# buttonModule.net
KiCad netlist of a schematic drawn in EAGLE
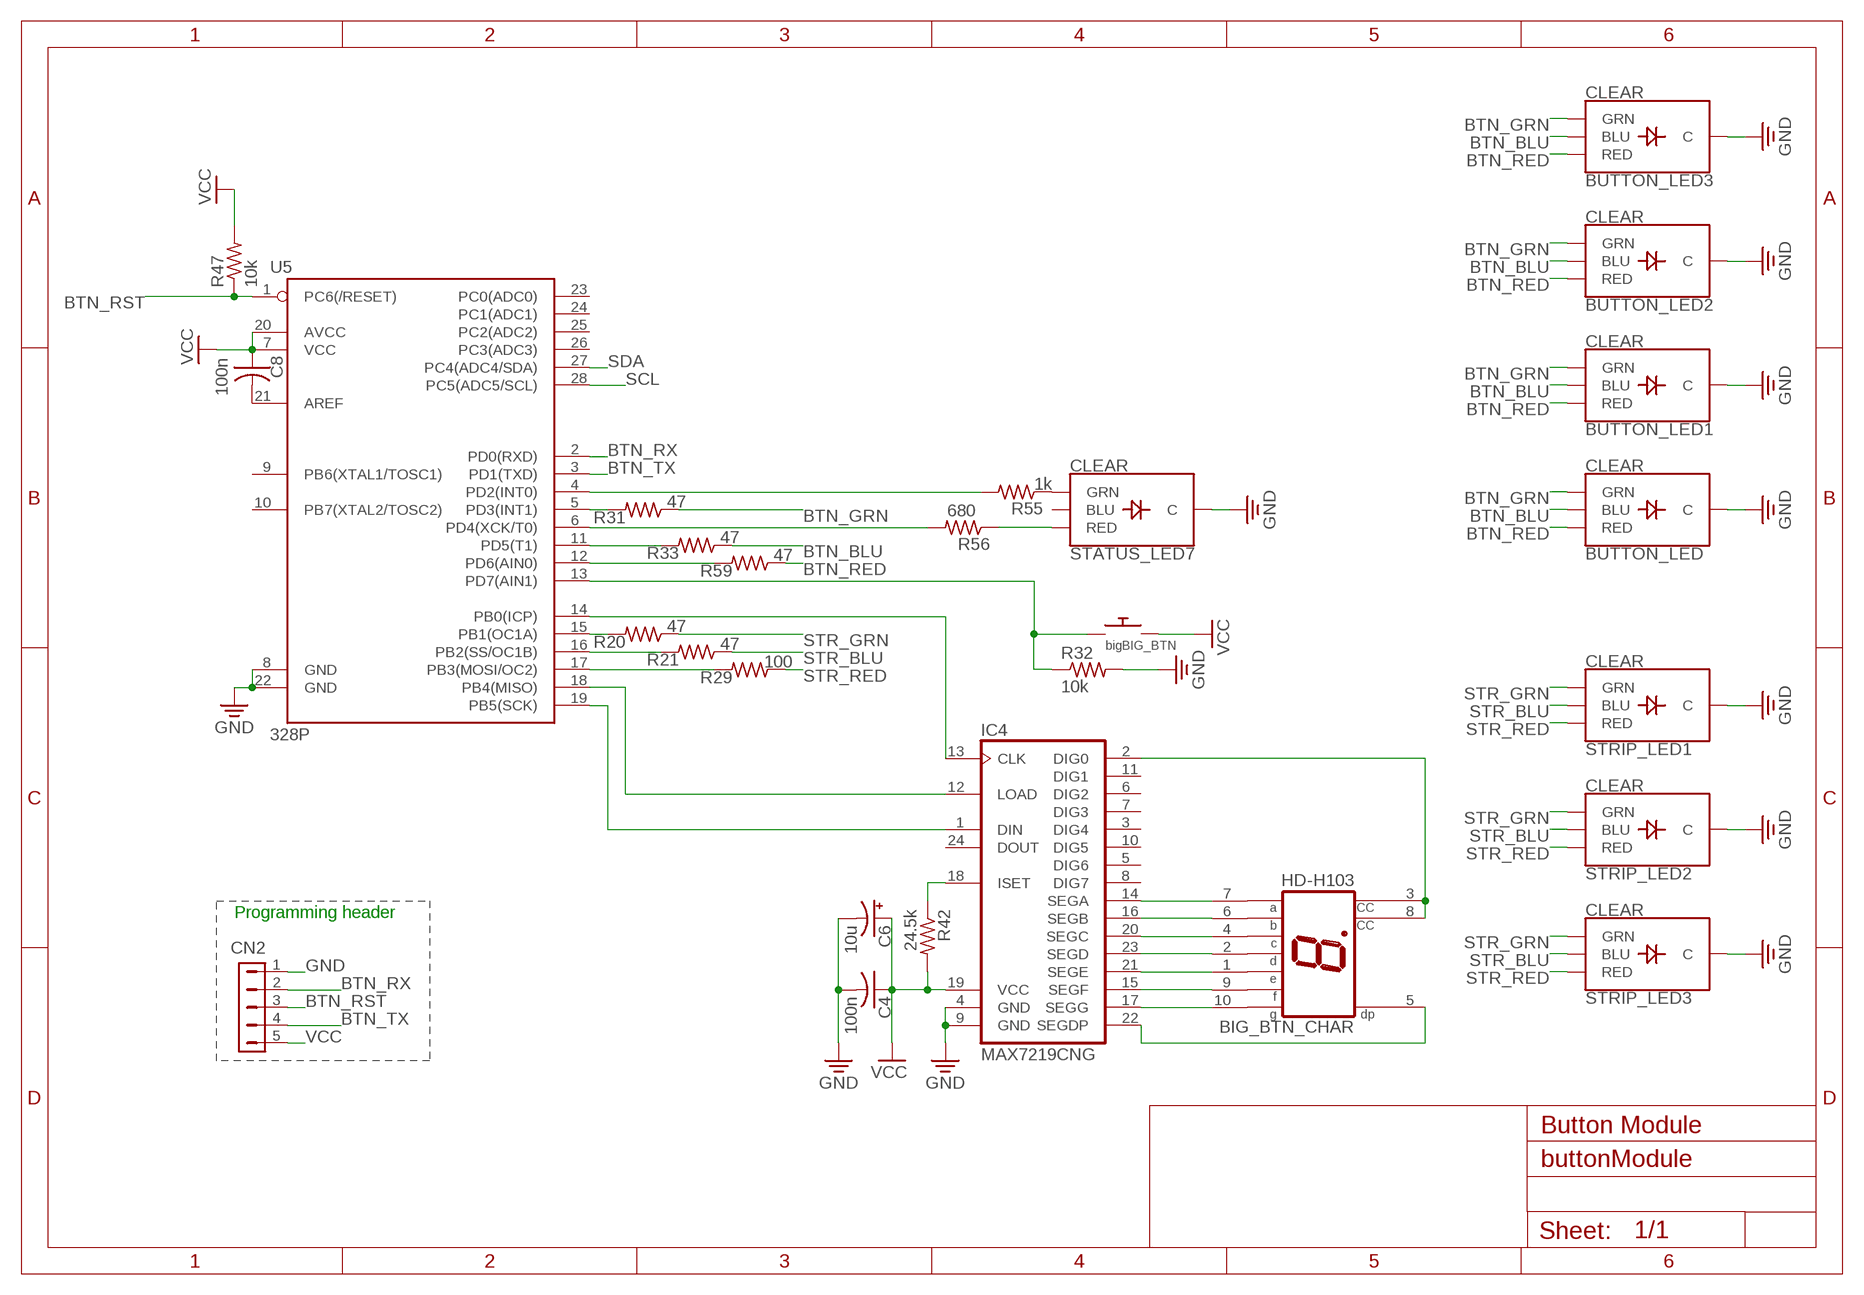
[diagram p0: schematic, sheet 1]

(export (version "E")
  (design (tool "Eeschema 10.0.6"))
  (components
    (comp (ref "BIG_BTN")
      (value "big")
      (footprint "eagle-import:TACT_PANA-EVQ")
      (libsource (lib "eagle-import") (part "SWITCH_PUSHBUTTONEVQ-PE"))
    )
    (comp (ref "BIG_BTN_CHAR")
      (value "HD-H103")
      (footprint "eagle-import:HDSP-M")
      (libsource (lib "eagle-import") (part "HD-H103"))
    )
    (comp (ref "BUTTON_LED")
      (value "CLEAR")
      (footprint "eagle-import:LED-RGB-THRU")
      (libsource (lib "eagle-import") (part "LED-RGB-CCCLEAR"))
    )
    (comp (ref "BUTTON_LED1")
      (value "CLEAR")
      (footprint "eagle-import:LED-RGB-THRU")
      (libsource (lib "eagle-import") (part "LED-RGB-CCCLEAR"))
    )
    (comp (ref "BUTTON_LED2")
      (value "CLEAR")
      (footprint "eagle-import:LED-RGB-THRU")
      (libsource (lib "eagle-import") (part "LED-RGB-CCCLEAR"))
    )
    (comp (ref "BUTTON_LED3")
      (value "CLEAR")
      (footprint "eagle-import:LED-RGB-THRU")
      (libsource (lib "eagle-import") (part "LED-RGB-CCCLEAR"))
    )
    (comp (ref "C4")
      (value "100n")
      (footprint "eagle-import:C025-024X044")
      (libsource (lib "eagle-import") (part "C-US025-024X044"))
    )
    (comp (ref "C6")
      (value "10u")
      (footprint "eagle-import:085CS_1AR")
      (libsource (lib "eagle-import") (part "CPOL-US085CS-1AR"))
    )
    (comp (ref "C8")
      (value "100n")
      (footprint "eagle-import:C025-024X044")
      (libsource (lib "eagle-import") (part "C-US025-024X044"))
    )
    (comp (ref "CN2")
      (value "HDR-1X5-SIP-100")
      (footprint "eagle-import:SIP-100-5V")
      (libsource (lib "eagle-import") (part "HDR-1X5-SIP-100"))
    )
    (comp (ref "IC4")
      (value "MAX7219CNG")
      (footprint "eagle-import:DIL24-3")
      (fields (field (name "MF") "MAXIM"))
      (libsource (lib "eagle-import") (part "MAX7219CNG"))
    )
    (comp (ref "R20")
      (value "47")
      (footprint "eagle-import:0805-THM")
      (libsource (lib "eagle-import") (part "FLIPFLOP-RES"))
    )
    (comp (ref "R21")
      (value "47")
      (footprint "eagle-import:0805-THM")
      (libsource (lib "eagle-import") (part "FLIPFLOP-RES"))
    )
    (comp (ref "R29")
      (value "100")
      (footprint "eagle-import:0805-THM")
      (libsource (lib "eagle-import") (part "FLIPFLOP-RES"))
    )
    (comp (ref "R31")
      (value "47")
      (footprint "eagle-import:0805-THM")
      (libsource (lib "eagle-import") (part "FLIPFLOP-RES"))
    )
    (comp (ref "R32")
      (value "10k")
      (footprint "eagle-import:0309_12")
      (libsource (lib "eagle-import") (part "R-US_0309/12"))
    )
    (comp (ref "R33")
      (value "47")
      (footprint "eagle-import:0805-THM")
      (libsource (lib "eagle-import") (part "FLIPFLOP-RES"))
    )
    (comp (ref "R42")
      (value "24.5k")
      (footprint "eagle-import:0309_12")
      (libsource (lib "eagle-import") (part "R-US_0309/12"))
    )
    (comp (ref "R47")
      (value "10k")
      (footprint "eagle-import:0309_12")
      (libsource (lib "eagle-import") (part "R-US_0309/12"))
    )
    (comp (ref "R55")
      (value "1k")
      (footprint "eagle-import:0805-THM")
      (libsource (lib "eagle-import") (part "FLIPFLOP-RES"))
    )
    (comp (ref "R56")
      (value "680")
      (footprint "eagle-import:0805-THM")
      (libsource (lib "eagle-import") (part "FLIPFLOP-RES"))
    )
    (comp (ref "R59")
      (value "47")
      (footprint "eagle-import:0805-THM")
      (libsource (lib "eagle-import") (part "FLIPFLOP-RES"))
    )
    (comp (ref "STATUS_LED7")
      (value "CLEAR")
      (footprint "eagle-import:LED-RGB-THRU")
      (libsource (lib "eagle-import") (part "LED-RGB-CCCLEAR"))
    )
    (comp (ref "STRIP_LED1")
      (value "CLEAR")
      (footprint "eagle-import:LED-RGB-THRU")
      (libsource (lib "eagle-import") (part "LED-RGB-CCCLEAR"))
    )
    (comp (ref "STRIP_LED2")
      (value "CLEAR")
      (footprint "eagle-import:LED-RGB-THRU")
      (libsource (lib "eagle-import") (part "LED-RGB-CCCLEAR"))
    )
    (comp (ref "STRIP_LED3")
      (value "CLEAR")
      (footprint "eagle-import:LED-RGB-THRU")
      (libsource (lib "eagle-import") (part "LED-RGB-CCCLEAR"))
    )
    (comp (ref "U5")
      (value "328P")
      (footprint "eagle-import:DIP28")
      (libsource (lib "eagle-import") (part "ATMEGA328P_PDIP"))
    )
  )
  (nets
    (net (code "1") (name "/BTN_BLU") (class "Default")
      (node (ref "BUTTON_LED") (pin "4") (pinfunction "BLU_4") (pintype "bidirectional"))
      (node (ref "BUTTON_LED1") (pin "4") (pinfunction "BLU_4") (pintype "bidirectional"))
      (node (ref "BUTTON_LED2") (pin "4") (pinfunction "BLU_4") (pintype "bidirectional"))
      (node (ref "BUTTON_LED3") (pin "4") (pinfunction "BLU_4") (pintype "bidirectional"))
      (node (ref "R33") (pin "1") (pinfunction "1_1") (pintype "passive"))
    )
    (net (code "2") (name "/BTN_GRN") (class "Default")
      (node (ref "BUTTON_LED") (pin "3") (pinfunction "GRN_3") (pintype "bidirectional"))
      (node (ref "BUTTON_LED1") (pin "3") (pinfunction "GRN_3") (pintype "bidirectional"))
      (node (ref "BUTTON_LED2") (pin "3") (pinfunction "GRN_3") (pintype "bidirectional"))
      (node (ref "BUTTON_LED3") (pin "3") (pinfunction "GRN_3") (pintype "bidirectional"))
      (node (ref "R31") (pin "1") (pinfunction "1_1") (pintype "passive"))
    )
    (net (code "3") (name "/BTN_RED") (class "Default")
      (node (ref "BUTTON_LED") (pin "1") (pinfunction "RED_1") (pintype "bidirectional"))
      (node (ref "BUTTON_LED1") (pin "1") (pinfunction "RED_1") (pintype "bidirectional"))
      (node (ref "BUTTON_LED2") (pin "1") (pinfunction "RED_1") (pintype "bidirectional"))
      (node (ref "BUTTON_LED3") (pin "1") (pinfunction "RED_1") (pintype "bidirectional"))
      (node (ref "R59") (pin "1") (pinfunction "1_1") (pintype "passive"))
    )
    (net (code "4") (name "/BTN_RST") (class "Default")
      (node (ref "CN2") (pin "3") (pinfunction "3_3") (pintype "passive"))
      (node (ref "R47") (pin "1") (pinfunction "1_1") (pintype "passive"))
      (node (ref "U5") (pin "1") (pinfunction "PC6(/RESET)_1") (pintype "bidirectional"))
    )
    (net (code "5") (name "/BTN_RX") (class "Default")
      (node (ref "CN2") (pin "2") (pinfunction "2_2") (pintype "passive"))
      (node (ref "U5") (pin "2") (pinfunction "PD0(RXD)_2") (pintype "bidirectional"))
    )
    (net (code "6") (name "/BTN_TX") (class "Default")
      (node (ref "CN2") (pin "4") (pinfunction "4_4") (pintype "passive"))
      (node (ref "U5") (pin "3") (pinfunction "PD1(TXD)_3") (pintype "bidirectional"))
    )
    (net (code "7") (name "/SCL") (class "Default")
      (node (ref "U5") (pin "28") (pinfunction "PC5(ADC5/SCL)_28") (pintype "bidirectional"))
    )
    (net (code "8") (name "/SDA") (class "Default")
      (node (ref "U5") (pin "27") (pinfunction "PC4(ADC4/SDA)_27") (pintype "bidirectional"))
    )
    (net (code "9") (name "/STR_BLU") (class "Default")
      (node (ref "R21") (pin "1") (pinfunction "1_1") (pintype "passive"))
      (node (ref "STRIP_LED1") (pin "4") (pinfunction "BLU_4") (pintype "bidirectional"))
      (node (ref "STRIP_LED2") (pin "4") (pinfunction "BLU_4") (pintype "bidirectional"))
      (node (ref "STRIP_LED3") (pin "4") (pinfunction "BLU_4") (pintype "bidirectional"))
    )
    (net (code "10") (name "/STR_GRN") (class "Default")
      (node (ref "R20") (pin "1") (pinfunction "1_1") (pintype "passive"))
      (node (ref "STRIP_LED1") (pin "3") (pinfunction "GRN_3") (pintype "bidirectional"))
      (node (ref "STRIP_LED2") (pin "3") (pinfunction "GRN_3") (pintype "bidirectional"))
      (node (ref "STRIP_LED3") (pin "3") (pinfunction "GRN_3") (pintype "bidirectional"))
    )
    (net (code "11") (name "/STR_RED") (class "Default")
      (node (ref "R29") (pin "1") (pinfunction "1_1") (pintype "passive"))
      (node (ref "STRIP_LED1") (pin "1") (pinfunction "RED_1") (pintype "bidirectional"))
      (node (ref "STRIP_LED2") (pin "1") (pinfunction "RED_1") (pintype "bidirectional"))
      (node (ref "STRIP_LED3") (pin "1") (pinfunction "RED_1") (pintype "bidirectional"))
    )
    (net (code "12") (name "GND") (class "Default")
      (node (ref "BUTTON_LED") (pin "2") (pinfunction "C_2") (pintype "bidirectional"))
      (node (ref "BUTTON_LED1") (pin "2") (pinfunction "C_2") (pintype "bidirectional"))
      (node (ref "BUTTON_LED2") (pin "2") (pinfunction "C_2") (pintype "bidirectional"))
      (node (ref "BUTTON_LED3") (pin "2") (pinfunction "C_2") (pintype "bidirectional"))
      (node (ref "C4") (pin "2") (pinfunction "2_2") (pintype "passive"))
      (node (ref "C6") (pin "-") (pinfunction "-_-") (pintype "passive"))
      (node (ref "CN2") (pin "1") (pinfunction "1_1") (pintype "passive"))
      (node (ref "IC4") (pin "4") (pinfunction "GND_4") (pintype "power_in"))
      (node (ref "IC4") (pin "9") (pinfunction "GND_9") (pintype "power_in"))
      (node (ref "R32") (pin "2") (pinfunction "2_2") (pintype "passive"))
      (node (ref "STATUS_LED7") (pin "2") (pinfunction "C_2") (pintype "bidirectional"))
      (node (ref "STRIP_LED1") (pin "2") (pinfunction "C_2") (pintype "bidirectional"))
      (node (ref "STRIP_LED2") (pin "2") (pinfunction "C_2") (pintype "bidirectional"))
      (node (ref "STRIP_LED3") (pin "2") (pinfunction "C_2") (pintype "bidirectional"))
      (node (ref "U5") (pin "22") (pinfunction "GND_22") (pintype "bidirectional"))
      (node (ref "U5") (pin "8") (pinfunction "GND_8") (pintype "bidirectional"))
    )
    (net (code "13") (name "Net-(BIG_BTN_CHAR-A)") (class "Default")
      (node (ref "BIG_BTN_CHAR") (pin "7") (pinfunction "A_7") (pintype "passive"))
      (node (ref "IC4") (pin "14") (pinfunction "SEGA_14") (pintype "output"))
    )
    (net (code "14") (name "Net-(BIG_BTN_CHAR-B)") (class "Default")
      (node (ref "BIG_BTN_CHAR") (pin "6") (pinfunction "B_6") (pintype "passive"))
      (node (ref "IC4") (pin "16") (pinfunction "SEGB_16") (pintype "output"))
    )
    (net (code "15") (name "Net-(BIG_BTN_CHAR-C)") (class "Default")
      (node (ref "BIG_BTN_CHAR") (pin "4") (pinfunction "C_4") (pintype "passive"))
      (node (ref "IC4") (pin "20") (pinfunction "SEGC_20") (pintype "output"))
    )
    (net (code "16") (name "Net-(BIG_BTN_CHAR-D)") (class "Default")
      (node (ref "BIG_BTN_CHAR") (pin "2") (pinfunction "D_2") (pintype "passive"))
      (node (ref "IC4") (pin "23") (pinfunction "SEGD_23") (pintype "output"))
    )
    (net (code "17") (name "Net-(BIG_BTN_CHAR-DP)") (class "Default")
      (node (ref "BIG_BTN_CHAR") (pin "5") (pinfunction "DP_5") (pintype "passive"))
      (node (ref "IC4") (pin "22") (pinfunction "SEGDP_22") (pintype "output"))
    )
    (net (code "18") (name "Net-(BIG_BTN_CHAR-E)") (class "Default")
      (node (ref "BIG_BTN_CHAR") (pin "1") (pinfunction "E_1") (pintype "passive"))
      (node (ref "IC4") (pin "21") (pinfunction "SEGE_21") (pintype "output"))
    )
    (net (code "19") (name "Net-(BIG_BTN_CHAR-F)") (class "Default")
      (node (ref "BIG_BTN_CHAR") (pin "9") (pinfunction "F_9") (pintype "passive"))
      (node (ref "IC4") (pin "15") (pinfunction "SEGF_15") (pintype "output"))
    )
    (net (code "20") (name "Net-(BIG_BTN_CHAR-G)") (class "Default")
      (node (ref "BIG_BTN_CHAR") (pin "10") (pinfunction "G_10") (pintype "passive"))
      (node (ref "IC4") (pin "17") (pinfunction "SEGG_17") (pintype "output"))
    )
    (net (code "21") (name "Net-(IC4-CLK)") (class "Default")
      (node (ref "IC4") (pin "13") (pinfunction "CLK_13") (pintype "input"))
      (node (ref "U5") (pin "14") (pinfunction "PB0(ICP)_14") (pintype "bidirectional"))
    )
    (net (code "22") (name "Net-(IC4-DIG0)") (class "Default")
      (node (ref "BIG_BTN_CHAR") (pin "3") (pinfunction "CC_3") (pintype "passive"))
      (node (ref "BIG_BTN_CHAR") (pin "8") (pinfunction "CC_8") (pintype "passive"))
      (node (ref "IC4") (pin "2") (pinfunction "DIG0_2") (pintype "output"))
    )
    (net (code "23") (name "Net-(IC4-DIN)") (class "Default")
      (node (ref "IC4") (pin "1") (pinfunction "DIN_1") (pintype "input"))
      (node (ref "U5") (pin "19") (pinfunction "PB5(SCK)_19") (pintype "bidirectional"))
    )
    (net (code "24") (name "Net-(IC4-ISET)") (class "Default")
      (node (ref "IC4") (pin "18") (pinfunction "ISET_18") (pintype "input"))
      (node (ref "R42") (pin "1") (pinfunction "1_1") (pintype "passive"))
    )
    (net (code "25") (name "Net-(IC4-LOAD)") (class "Default")
      (node (ref "IC4") (pin "12") (pinfunction "LOAD_12") (pintype "input"))
      (node (ref "U5") (pin "18") (pinfunction "PB4(MISO)_18") (pintype "bidirectional"))
    )
    (net (code "26") (name "Net-(STATUS_LED7-GRN)") (class "Default")
      (node (ref "R55") (pin "1") (pinfunction "1_1") (pintype "passive"))
      (node (ref "STATUS_LED7") (pin "3") (pinfunction "GRN_3") (pintype "bidirectional"))
    )
    (net (code "27") (name "Net-(STATUS_LED7-RED)") (class "Default")
      (node (ref "R56") (pin "1") (pinfunction "1_1") (pintype "passive"))
      (node (ref "STATUS_LED7") (pin "1") (pinfunction "RED_1") (pintype "bidirectional"))
    )
    (net (code "28") (name "Net-(U5-AREF)") (class "Default")
      (node (ref "C8") (pin "2") (pinfunction "2_2") (pintype "passive"))
      (node (ref "U5") (pin "21") (pinfunction "AREF_21") (pintype "bidirectional"))
    )
    (net (code "29") (name "Net-(U5-PB1(OC1A))") (class "Default")
      (node (ref "R20") (pin "2") (pinfunction "2_2") (pintype "passive"))
      (node (ref "U5") (pin "15") (pinfunction "PB1(OC1A)_15") (pintype "bidirectional"))
    )
    (net (code "30") (name "Net-(U5-PB2(SS{slash}OC1B))") (class "Default")
      (node (ref "R21") (pin "2") (pinfunction "2_2") (pintype "passive"))
      (node (ref "U5") (pin "16") (pinfunction "PB2(SS/OC1B)_16") (pintype "bidirectional"))
    )
    (net (code "31") (name "Net-(U5-PB3(MOSI{slash}OC2))") (class "Default")
      (node (ref "R29") (pin "2") (pinfunction "2_2") (pintype "passive"))
      (node (ref "U5") (pin "17") (pinfunction "PB3(MOSI/OC2)_17") (pintype "bidirectional"))
    )
    (net (code "32") (name "Net-(U5-PD2(INT0))") (class "Default")
      (node (ref "R55") (pin "2") (pinfunction "2_2") (pintype "passive"))
      (node (ref "U5") (pin "4") (pinfunction "PD2(INT0)_4") (pintype "bidirectional"))
    )
    (net (code "33") (name "Net-(U5-PD3(INT1))") (class "Default")
      (node (ref "R31") (pin "2") (pinfunction "2_2") (pintype "passive"))
      (node (ref "U5") (pin "5") (pinfunction "PD3(INT1)_5") (pintype "bidirectional"))
    )
    (net (code "34") (name "Net-(U5-PD4(XCK{slash}T0))") (class "Default")
      (node (ref "R56") (pin "2") (pinfunction "2_2") (pintype "passive"))
      (node (ref "U5") (pin "6") (pinfunction "PD4(XCK/T0)_6") (pintype "bidirectional"))
    )
    (net (code "35") (name "Net-(U5-PD5(T1))") (class "Default")
      (node (ref "R33") (pin "2") (pinfunction "2_2") (pintype "passive"))
      (node (ref "U5") (pin "11") (pinfunction "PD5(T1)_11") (pintype "bidirectional"))
    )
    (net (code "36") (name "Net-(U5-PD6(AIN0))") (class "Default")
      (node (ref "R59") (pin "2") (pinfunction "2_2") (pintype "passive"))
      (node (ref "U5") (pin "12") (pinfunction "PD6(AIN0)_12") (pintype "bidirectional"))
    )
    (net (code "37") (name "Net-(U5-PD7(AIN1))") (class "Default")
      (node (ref "BIG_BTN") (pin "P$1") (pinfunction "P$1_P$1") (pintype "passive"))
      (node (ref "R32") (pin "1") (pinfunction "1_1") (pintype "passive"))
      (node (ref "U5") (pin "13") (pinfunction "PD7(AIN1)_13") (pintype "bidirectional"))
    )
    (net (code "38") (name "VCC") (class "Default")
      (node (ref "BIG_BTN") (pin "P$2") (pinfunction "P$2_P$2") (pintype "passive"))
      (node (ref "C4") (pin "1") (pinfunction "1_1") (pintype "passive"))
      (node (ref "C6") (pin "+") (pinfunction "+_+") (pintype "passive"))
      (node (ref "C8") (pin "1") (pinfunction "1_1") (pintype "passive"))
      (node (ref "CN2") (pin "5") (pinfunction "5_5") (pintype "passive"))
      (node (ref "IC4") (pin "19") (pinfunction "VCC_19") (pintype "power_in"))
      (node (ref "R42") (pin "2") (pinfunction "2_2") (pintype "passive"))
      (node (ref "R47") (pin "2") (pinfunction "2_2") (pintype "passive"))
      (node (ref "U5") (pin "20") (pinfunction "AVCC_20") (pintype "bidirectional"))
      (node (ref "U5") (pin "7") (pinfunction "VCC_7") (pintype "bidirectional"))
    )
    (net (code "39") (name "unconnected-(IC4-DIG1-Pad11)") (class "Default")
      (node (ref "IC4") (pin "11") (pinfunction "DIG1_11") (pintype "output"))
    )
    (net (code "40") (name "unconnected-(IC4-DIG2-Pad6)") (class "Default")
      (node (ref "IC4") (pin "6") (pinfunction "DIG2_6") (pintype "output"))
    )
    (net (code "41") (name "unconnected-(IC4-DIG3-Pad7)") (class "Default")
      (node (ref "IC4") (pin "7") (pinfunction "DIG3_7") (pintype "output"))
    )
    (net (code "42") (name "unconnected-(IC4-DIG4-Pad3)") (class "Default")
      (node (ref "IC4") (pin "3") (pinfunction "DIG4_3") (pintype "output"))
    )
    (net (code "43") (name "unconnected-(IC4-DIG5-Pad10)") (class "Default")
      (node (ref "IC4") (pin "10") (pinfunction "DIG5_10") (pintype "output"))
    )
    (net (code "44") (name "unconnected-(IC4-DIG6-Pad5)") (class "Default")
      (node (ref "IC4") (pin "5") (pinfunction "DIG6_5") (pintype "output"))
    )
    (net (code "45") (name "unconnected-(IC4-DIG7-Pad8)") (class "Default")
      (node (ref "IC4") (pin "8") (pinfunction "DIG7_8") (pintype "output"))
    )
    (net (code "46") (name "unconnected-(IC4-DOUT-Pad24)") (class "Default")
      (node (ref "IC4") (pin "24") (pinfunction "DOUT_24") (pintype "output"))
    )
    (net (code "47") (name "unconnected-(STATUS_LED7-BLU-Pad4)") (class "Default")
      (node (ref "STATUS_LED7") (pin "4") (pinfunction "BLU_4") (pintype "bidirectional"))
    )
    (net (code "48") (name "unconnected-(U5-PB6(XTAL1{slash}TOSC1)-Pad9)") (class "Default")
      (node (ref "U5") (pin "9") (pinfunction "PB6(XTAL1/TOSC1)_9") (pintype "bidirectional"))
    )
    (net (code "49") (name "unconnected-(U5-PB7(XTAL2{slash}TOSC2)-Pad10)") (class "Default")
      (node (ref "U5") (pin "10") (pinfunction "PB7(XTAL2/TOSC2)_10") (pintype "bidirectional"))
    )
    (net (code "50") (name "unconnected-(U5-PC0(ADC0)-Pad23)") (class "Default")
      (node (ref "U5") (pin "23") (pinfunction "PC0(ADC0)_23") (pintype "bidirectional"))
    )
    (net (code "51") (name "unconnected-(U5-PC1(ADC1)-Pad24)") (class "Default")
      (node (ref "U5") (pin "24") (pinfunction "PC1(ADC1)_24") (pintype "bidirectional"))
    )
    (net (code "52") (name "unconnected-(U5-PC2(ADC2)-Pad25)") (class "Default")
      (node (ref "U5") (pin "25") (pinfunction "PC2(ADC2)_25") (pintype "bidirectional"))
    )
    (net (code "53") (name "unconnected-(U5-PC3(ADC3)-Pad26)") (class "Default")
      (node (ref "U5") (pin "26") (pinfunction "PC3(ADC3)_26") (pintype "bidirectional"))
    )
  )
)
